# FPGA_Banks_44_45_46_DDR64.net
KiCad netlist of a schematic drawn in Altium Designer
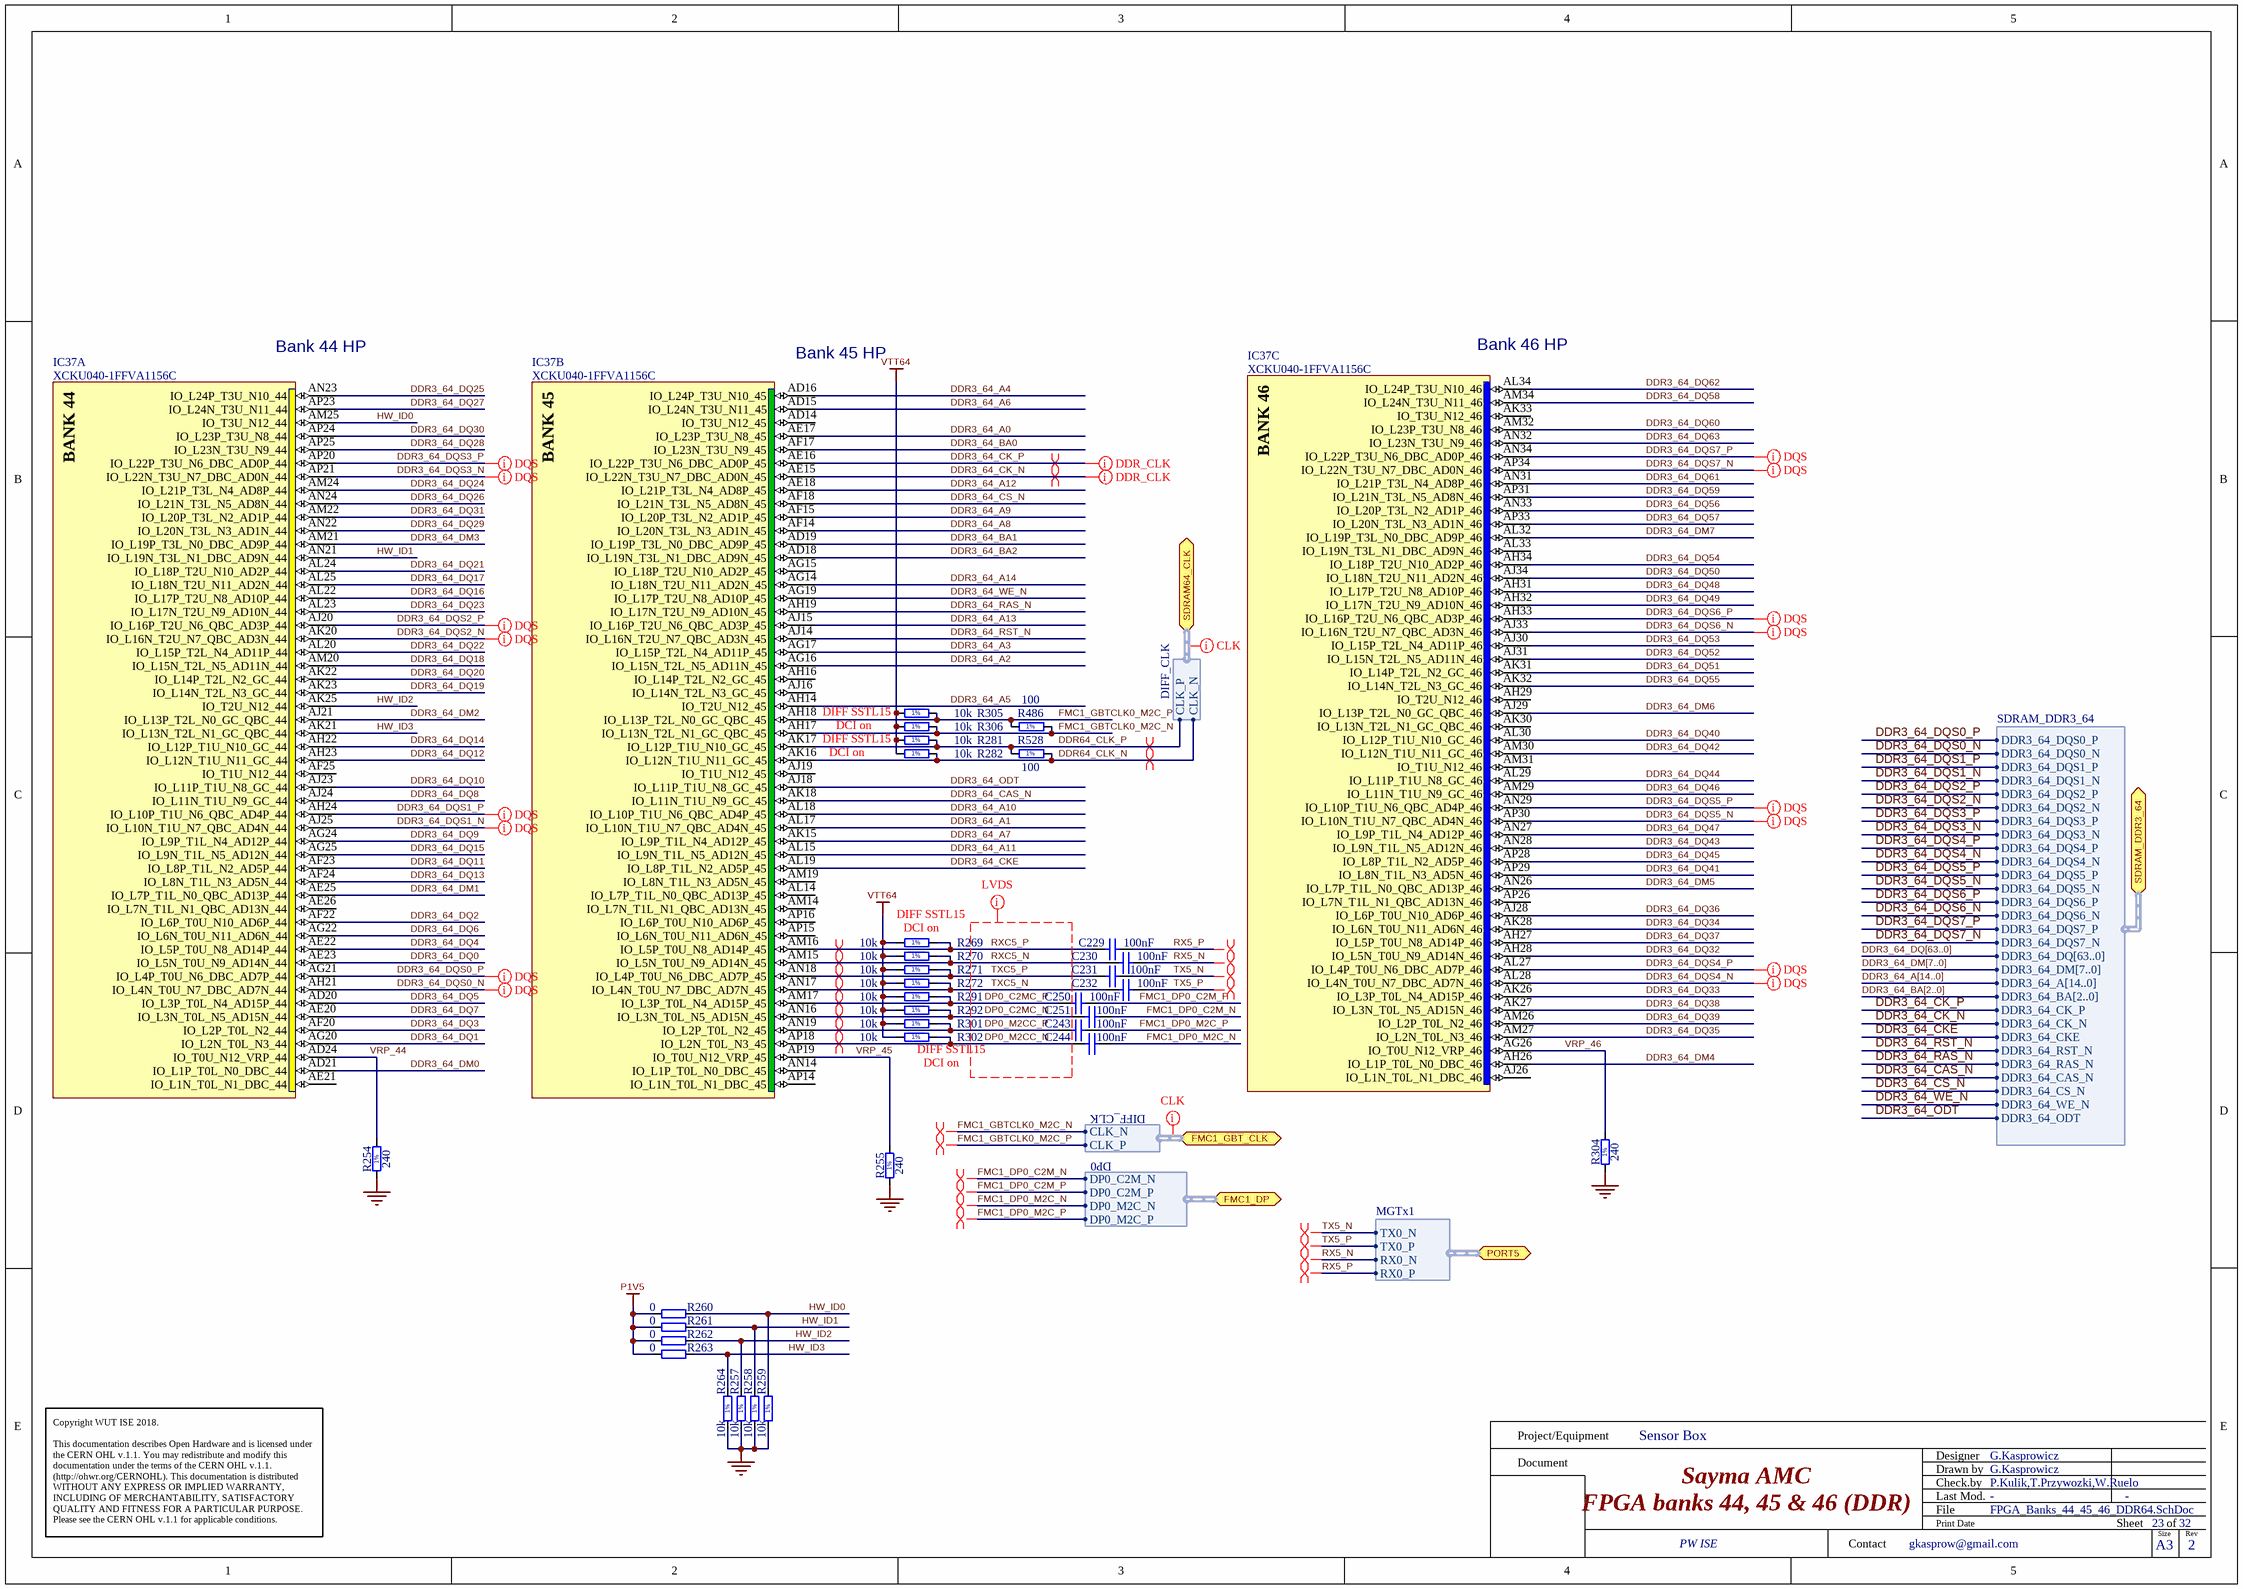
[diagram p0: FPGA_Banks_44_45_46_DDR64.SchDoc]

(export (version "E")
  (design (tool "Eeschema 10.0.6"))
  (components
    (comp (ref "C229")
      (value "100nF")
      (footprint "CAPC0603X33N")
      (description "Non-polarised capacitor")
      (fields
        (field (name "MANUFACTURER PART NUMBER") "CC0201_100NF_6.3V_10%_X5R")
        (field (name "MANUFACTURER") "GENERIC")
        (field (name "AUTHOR") "CERN DEM JLC")
      )
      (libsource (lib "Capacitors") (part "Capacitor - non polarized"))
    )
    (comp (ref "C230")
      (value "100nF")
      (footprint "CAPC0603X33N")
      (description "Non-polarised capacitor")
      (fields
        (field (name "MANUFACTURER PART NUMBER") "CC0201_100NF_6.3V_10%_X5R")
        (field (name "MANUFACTURER") "GENERIC")
        (field (name "AUTHOR") "CERN DEM JLC")
      )
      (libsource (lib "Capacitors") (part "Capacitor - non polarized"))
    )
    (comp (ref "C231")
      (value "100nF")
      (footprint "CAPC0603X33N")
      (description "Non-polarised capacitor")
      (fields
        (field (name "MANUFACTURER PART NUMBER") "CC0201_100NF_6.3V_10%_X5R")
        (field (name "MANUFACTURER") "GENERIC")
        (field (name "AUTHOR") "CERN DEM JLC")
      )
      (libsource (lib "Capacitors") (part "Capacitor - non polarized"))
    )
    (comp (ref "C232")
      (value "100nF")
      (footprint "CAPC0603X33N")
      (description "Non-polarised capacitor")
      (fields
        (field (name "MANUFACTURER PART NUMBER") "CC0201_100NF_6.3V_10%_X5R")
        (field (name "MANUFACTURER") "GENERIC")
        (field (name "AUTHOR") "CERN DEM JLC")
      )
      (libsource (lib "Capacitors") (part "Capacitor - non polarized"))
    )
    (comp (ref "C243")
      (value "100nF")
      (footprint "CAPC0603X33N")
      (description "Non-polarised capacitor")
      (fields
        (field (name "MANUFACTURER PART NUMBER") "CC0201_100NF_6.3V_10%_X5R")
        (field (name "MANUFACTURER") "GENERIC")
        (field (name "AUTHOR") "CERN DEM JLC")
      )
      (libsource (lib "Capacitors") (part "Capacitor - non polarized"))
    )
    (comp (ref "C244")
      (value "100nF")
      (footprint "CAPC0603X33N")
      (description "Non-polarised capacitor")
      (fields
        (field (name "MANUFACTURER PART NUMBER") "CC0201_100NF_6.3V_10%_X5R")
        (field (name "MANUFACTURER") "GENERIC")
        (field (name "AUTHOR") "CERN DEM JLC")
      )
      (libsource (lib "Capacitors") (part "Capacitor - non polarized"))
    )
    (comp (ref "C250")
      (value "100nF")
      (footprint "CAPC0603X33N")
      (description "Non-polarised capacitor")
      (fields
        (field (name "MANUFACTURER PART NUMBER") "CC0201_100NF_6.3V_10%_X5R")
        (field (name "MANUFACTURER") "GENERIC")
        (field (name "AUTHOR") "CERN DEM JLC")
      )
      (libsource (lib "Capacitors") (part "Capacitor - non polarized"))
    )
    (comp (ref "C251")
      (value "100nF")
      (footprint "CAPC0603X33N")
      (description "Non-polarised capacitor")
      (fields
        (field (name "MANUFACTURER PART NUMBER") "CC0201_100NF_6.3V_10%_X5R")
        (field (name "MANUFACTURER") "GENERIC")
        (field (name "AUTHOR") "CERN DEM JLC")
      )
      (libsource (lib "Capacitors") (part "Capacitor - non polarized"))
    )
    (comp (ref "IC37")
      (value "XCKU040-1FFVA1156C")
      (footprint "BGA1156C100P34X34_3500X3500X350")
      (description "Kintex UltraScale FPGA, 520 I/O, 530K Cells, 1156-Ball BGA, Speed Grade 1, Commercial Grade")
      (fields (field (name "MANUFACTURER") "XILINX") (field (name "AUTHOR") "CERN DEM CA"))
      (libsource (lib "ICs And Semiconductors") (part "XCKU040-1FFVA1156C"))
    )
    (comp (ref "R254")
      (value "240")
      (footprint "RESC1005X40N")
      (description "Resistor - 1%")
      (fields
        (field (name "MANUFACTURER PART NUMBER") "R0402_240R_1%_0.0625W_100PPM")
        (field (name "MANUFACTURER") "GENERIC")
        (field (name "AUTHOR") "CERN DEM JLC")
      )
      (libsource (lib "Resistors") (part "Resistor - 1%"))
    )
    (comp (ref "R255")
      (value "240")
      (footprint "RESC1005X40N")
      (description "Resistor - 1%")
      (fields
        (field (name "MANUFACTURER PART NUMBER") "R0402_240R_1%_0.0625W_100PPM")
        (field (name "MANUFACTURER") "GENERIC")
        (field (name "AUTHOR") "CERN DEM JLC")
      )
      (libsource (lib "Resistors") (part "Resistor - 1%"))
    )
    (comp (ref "R257")
      (value "10k")
      (footprint "RESC1005X40N")
      (description "Resistor - 1%")
      (fields
        (field (name "MANUFACTURER PART NUMBER") "R0402_10K_1%_0.0625W_100PPM")
        (field (name "MANUFACTURER") "GENERIC")
        (field (name "AUTHOR") "CERN DEM JLC")
      )
      (libsource (lib "Resistors") (part "Resistor - 1%"))
    )
    (comp (ref "R258")
      (value "10k")
      (footprint "RESC1005X40N")
      (description "Resistor - 1%")
      (fields
        (field (name "MANUFACTURER PART NUMBER") "R0402_10K_1%_0.0625W_100PPM")
        (field (name "MANUFACTURER") "GENERIC")
        (field (name "AUTHOR") "CERN DEM JLC")
      )
      (libsource (lib "Resistors") (part "Resistor - 1%"))
    )
    (comp (ref "R259")
      (value "10k")
      (footprint "RESC1005X40N")
      (description "Resistor - 1%")
      (fields
        (field (name "MANUFACTURER PART NUMBER") "R0402_10K_1%_0.0625W_100PPM")
        (field (name "MANUFACTURER") "GENERIC")
        (field (name "AUTHOR") "CERN DEM JLC")
      )
      (libsource (lib "Resistors") (part "Resistor - 1%"))
    )
    (comp (ref "R260")
      (value "0")
      (footprint "RESC1005X40N")
      (description "Resistor")
      (fields
        (field (name "MANUFACTURER PART NUMBER") "R0402_0R_JUMPER")
        (field (name "MANUFACTURER") "GENERIC")
        (field (name "AUTHOR") "CERN DEM JLC")
      )
      (libsource (lib "Resistors") (part "Resistor"))
    )
    (comp (ref "R261")
      (value "0")
      (footprint "RESC1005X40N")
      (description "Resistor")
      (fields
        (field (name "MANUFACTURER PART NUMBER") "R0402_0R_JUMPER")
        (field (name "MANUFACTURER") "GENERIC")
        (field (name "AUTHOR") "CERN DEM JLC")
      )
      (libsource (lib "Resistors") (part "Resistor"))
    )
    (comp (ref "R262")
      (value "0")
      (footprint "RESC1005X40N")
      (description "Resistor")
      (fields
        (field (name "MANUFACTURER PART NUMBER") "R0402_0R_JUMPER")
        (field (name "MANUFACTURER") "GENERIC")
        (field (name "AUTHOR") "CERN DEM JLC")
      )
      (libsource (lib "Resistors") (part "Resistor"))
    )
    (comp (ref "R263")
      (value "0")
      (footprint "RESC1005X40N")
      (description "Resistor")
      (fields
        (field (name "MANUFACTURER PART NUMBER") "R0402_0R_JUMPER")
        (field (name "MANUFACTURER") "GENERIC")
        (field (name "AUTHOR") "CERN DEM JLC")
      )
      (libsource (lib "Resistors") (part "Resistor"))
    )
    (comp (ref "R264")
      (value "10k")
      (footprint "RESC1005X40N")
      (description "Resistor - 1%")
      (fields
        (field (name "MANUFACTURER PART NUMBER") "R0402_10K_1%_0.0625W_100PPM")
        (field (name "MANUFACTURER") "GENERIC")
        (field (name "AUTHOR") "CERN DEM JLC")
      )
      (libsource (lib "Resistors") (part "Resistor - 1%"))
    )
    (comp (ref "R269")
      (value "10k")
      (footprint "RESC1005X40N")
      (description "Resistor - 1%")
      (fields
        (field (name "MANUFACTURER PART NUMBER") "R0402_10K_1%_0.0625W_100PPM")
        (field (name "MANUFACTURER") "GENERIC")
        (field (name "AUTHOR") "CERN DEM JLC")
      )
      (libsource (lib "Resistors") (part "Resistor - 1%"))
    )
    (comp (ref "R270")
      (value "10k")
      (footprint "RESC1005X40N")
      (description "Resistor - 1%")
      (fields
        (field (name "MANUFACTURER PART NUMBER") "R0402_10K_1%_0.0625W_100PPM")
        (field (name "MANUFACTURER") "GENERIC")
        (field (name "AUTHOR") "CERN DEM JLC")
      )
      (libsource (lib "Resistors") (part "Resistor - 1%"))
    )
    (comp (ref "R271")
      (value "10k")
      (footprint "RESC1005X40N")
      (description "Resistor - 1%")
      (fields
        (field (name "MANUFACTURER PART NUMBER") "R0402_10K_1%_0.0625W_100PPM")
        (field (name "MANUFACTURER") "GENERIC")
        (field (name "AUTHOR") "CERN DEM JLC")
      )
      (libsource (lib "Resistors") (part "Resistor - 1%"))
    )
    (comp (ref "R272")
      (value "10k")
      (footprint "RESC1005X40N")
      (description "Resistor - 1%")
      (fields
        (field (name "MANUFACTURER PART NUMBER") "R0402_10K_1%_0.0625W_100PPM")
        (field (name "MANUFACTURER") "GENERIC")
        (field (name "AUTHOR") "CERN DEM JLC")
      )
      (libsource (lib "Resistors") (part "Resistor - 1%"))
    )
    (comp (ref "R281")
      (value "10k")
      (footprint "RESC1005X40N")
      (description "Resistor - 1%")
      (fields
        (field (name "MANUFACTURER PART NUMBER") "R0402_10K_1%_0.0625W_100PPM")
        (field (name "MANUFACTURER") "GENERIC")
        (field (name "AUTHOR") "CERN DEM JLC")
      )
      (libsource (lib "Resistors") (part "Resistor - 1%"))
    )
    (comp (ref "R282")
      (value "10k")
      (footprint "RESC1005X40N")
      (description "Resistor - 1%")
      (fields
        (field (name "MANUFACTURER PART NUMBER") "R0402_10K_1%_0.0625W_100PPM")
        (field (name "MANUFACTURER") "GENERIC")
        (field (name "AUTHOR") "CERN DEM JLC")
      )
      (libsource (lib "Resistors") (part "Resistor - 1%"))
    )
    (comp (ref "R291")
      (value "10k")
      (footprint "RESC1005X40N")
      (description "Resistor - 1%")
      (fields
        (field (name "MANUFACTURER PART NUMBER") "R0402_10K_1%_0.0625W_100PPM")
        (field (name "MANUFACTURER") "GENERIC")
        (field (name "AUTHOR") "CERN DEM JLC")
      )
      (libsource (lib "Resistors") (part "Resistor - 1%"))
    )
    (comp (ref "R292")
      (value "10k")
      (footprint "RESC1005X40N")
      (description "Resistor - 1%")
      (fields
        (field (name "MANUFACTURER PART NUMBER") "R0402_10K_1%_0.0625W_100PPM")
        (field (name "MANUFACTURER") "GENERIC")
        (field (name "AUTHOR") "CERN DEM JLC")
      )
      (libsource (lib "Resistors") (part "Resistor - 1%"))
    )
    (comp (ref "R301")
      (value "10k")
      (footprint "RESC1005X40N")
      (description "Resistor - 1%")
      (fields
        (field (name "MANUFACTURER PART NUMBER") "R0402_10K_1%_0.0625W_100PPM")
        (field (name "MANUFACTURER") "GENERIC")
        (field (name "AUTHOR") "CERN DEM JLC")
      )
      (libsource (lib "Resistors") (part "Resistor - 1%"))
    )
    (comp (ref "R302")
      (value "10k")
      (footprint "RESC1005X40N")
      (description "Resistor - 1%")
      (fields
        (field (name "MANUFACTURER PART NUMBER") "R0402_10K_1%_0.0625W_100PPM")
        (field (name "MANUFACTURER") "GENERIC")
        (field (name "AUTHOR") "CERN DEM JLC")
      )
      (libsource (lib "Resistors") (part "Resistor - 1%"))
    )
    (comp (ref "R304")
      (value "240")
      (footprint "RESC1005X40N")
      (description "Resistor - 1%")
      (fields
        (field (name "MANUFACTURER PART NUMBER") "R0402_240R_1%_0.0625W_100PPM")
        (field (name "MANUFACTURER") "GENERIC")
        (field (name "AUTHOR") "CERN DEM JLC")
      )
      (libsource (lib "Resistors") (part "Resistor - 1%"))
    )
    (comp (ref "R305")
      (value "10k")
      (footprint "RESC1005X40N")
      (description "Resistor - 1%")
      (fields
        (field (name "MANUFACTURER PART NUMBER") "R0402_10K_1%_0.0625W_100PPM")
        (field (name "MANUFACTURER") "GENERIC")
        (field (name "AUTHOR") "CERN DEM JLC")
      )
      (libsource (lib "Resistors") (part "Resistor - 1%"))
    )
    (comp (ref "R306")
      (value "10k")
      (footprint "RESC1005X40N")
      (description "Resistor - 1%")
      (fields
        (field (name "MANUFACTURER PART NUMBER") "R0402_10K_1%_0.0625W_100PPM")
        (field (name "MANUFACTURER") "GENERIC")
        (field (name "AUTHOR") "CERN DEM JLC")
      )
      (libsource (lib "Resistors") (part "Resistor - 1%"))
    )
    (comp (ref "R486")
      (value "100")
      (footprint "RESC0603X28N")
      (description "Resistor - 1%")
      (fields
        (field (name "MANUFACTURER PART NUMBER") "R0201_100R_1%_0.05W_200PPM")
        (field (name "MANUFACTURER") "GENERIC")
        (field (name "AUTHOR") "CERN DEM JLC")
      )
      (libsource (lib "Resistors") (part "Resistor - 1%"))
    )
    (comp (ref "R528")
      (value "100")
      (footprint "RESC0603X28N")
      (description "Resistor - 1%")
      (fields
        (field (name "MANUFACTURER PART NUMBER") "R0201_100R_1%_0.05W_200PPM")
        (field (name "MANUFACTURER") "GENERIC")
        (field (name "AUTHOR") "CERN DEM JLC")
      )
      (libsource (lib "Resistors") (part "Resistor - 1%"))
    )
  )
  (nets
    (net (code "5") (name "/DDR3_64_A0") (class "Default")
      (node (ref "IC37") (pin "AE17") (pinfunction "IO_L23P_T3U_N8_45_AE17") (pintype "bidirectional"))
    )
    (net (code "6") (name "/DDR3_64_A1") (class "Default")
      (node (ref "IC37") (pin "AL17") (pinfunction "IO_L10N_T1U_N7_QBC_AD4N_45_AL17") (pintype "bidirectional"))
    )
    (net (code "7") (name "/DDR3_64_A2") (class "Default")
      (node (ref "IC37") (pin "AG16") (pinfunction "IO_L15N_T2L_N5_AD11N_45_AG16") (pintype "bidirectional"))
    )
    (net (code "8") (name "/DDR3_64_A3") (class "Default")
      (node (ref "IC37") (pin "AG17") (pinfunction "IO_L15P_T2L_N4_AD11P_45_AG17") (pintype "bidirectional"))
    )
    (net (code "9") (name "/DDR3_64_A4") (class "Default")
      (node (ref "IC37") (pin "AD16") (pinfunction "IO_L24P_T3U_N10_45_AD16") (pintype "bidirectional"))
    )
    (net (code "10") (name "/DDR3_64_A5") (class "Default")
      (node (ref "IC37") (pin "AH14") (pinfunction "IO_T2U_N12_45_AH14") (pintype "bidirectional"))
    )
    (net (code "11") (name "/DDR3_64_A6") (class "Default")
      (node (ref "IC37") (pin "AD15") (pinfunction "IO_L24N_T3U_N11_45_AD15") (pintype "bidirectional"))
    )
    (net (code "12") (name "/DDR3_64_A7") (class "Default")
      (node (ref "IC37") (pin "AK15") (pinfunction "IO_L9P_T1L_N4_AD12P_45_AK15") (pintype "bidirectional"))
    )
    (net (code "13") (name "/DDR3_64_A8") (class "Default")
      (node (ref "IC37") (pin "AF14") (pinfunction "IO_L20N_T3L_N3_AD1N_45_AF14") (pintype "bidirectional"))
    )
    (net (code "14") (name "/DDR3_64_A9") (class "Default")
      (node (ref "IC37") (pin "AF15") (pinfunction "IO_L20P_T3L_N2_AD1P_45_AF15") (pintype "bidirectional"))
    )
    (net (code "15") (name "/DDR3_64_A10") (class "Default")
      (node (ref "IC37") (pin "AL18") (pinfunction "IO_L10P_T1U_N6_QBC_AD4P_45_AL18") (pintype "bidirectional"))
    )
    (net (code "16") (name "/DDR3_64_A11") (class "Default")
      (node (ref "IC37") (pin "AL15") (pinfunction "IO_L9N_T1L_N5_AD12N_45_AL15") (pintype "bidirectional"))
    )
    (net (code "17") (name "/DDR3_64_A12") (class "Default")
      (node (ref "IC37") (pin "AE18") (pinfunction "IO_L21P_T3L_N4_AD8P_45_AE18") (pintype "bidirectional"))
    )
    (net (code "18") (name "/DDR3_64_A13") (class "Default")
      (node (ref "IC37") (pin "AJ15") (pinfunction "IO_L16P_T2U_N6_QBC_AD3P_45_AJ15") (pintype "bidirectional"))
    )
    (net (code "19") (name "/DDR3_64_A14") (class "Default")
      (node (ref "IC37") (pin "AG14") (pinfunction "IO_L18N_T2U_N11_AD2N_45_AG14") (pintype "bidirectional"))
    )
    (net (code "21") (name "/DDR3_64_BA0") (class "Default")
      (node (ref "IC37") (pin "AF17") (pinfunction "IO_L23N_T3U_N9_45_AF17") (pintype "bidirectional"))
    )
    (net (code "22") (name "/DDR3_64_BA1") (class "Default")
      (node (ref "IC37") (pin "AD19") (pinfunction "IO_L19P_T3L_N0_DBC_AD9P_45_AD19") (pintype "bidirectional"))
    )
    (net (code "23") (name "/DDR3_64_BA2") (class "Default")
      (node (ref "IC37") (pin "AD18") (pinfunction "IO_L19N_T3L_N1_DBC_AD9N_45_AD18") (pintype "bidirectional"))
    )
    (net (code "25") (name "/DDR3_64_CAS_N") (class "Default")
      (node (ref "IC37") (pin "AK18") (pinfunction "IO_L11N_T1U_N9_GC_45_AK18") (pintype "bidirectional"))
    )
    (net (code "26") (name "/DDR3_64_CKE") (class "Default")
      (node (ref "IC37") (pin "AL19") (pinfunction "IO_L8P_T1L_N2_AD5P_45_AL19") (pintype "bidirectional"))
    )
    (net (code "27") (name "/DDR3_64_CK_N") (class "Default")
      (node (ref "IC37") (pin "AE15") (pinfunction "IO_L22N_T3U_N7_DBC_AD0N_45_AE15") (pintype "bidirectional"))
    )
    (net (code "28") (name "/DDR3_64_CK_P") (class "Default")
      (node (ref "IC37") (pin "AE16") (pinfunction "IO_L22P_T3U_N6_DBC_AD0P_45_AE16") (pintype "bidirectional"))
    )
    (net (code "29") (name "/DDR3_64_CS_N") (class "Default")
      (node (ref "IC37") (pin "AF18") (pinfunction "IO_L21N_T3L_N5_AD8N_45_AF18") (pintype "bidirectional"))
    )
    (net (code "30") (name "/DDR3_64_DM0") (class "Default")
      (node (ref "IC37") (pin "AD21") (pinfunction "IO_L1P_T0L_N0_DBC_44_AD21") (pintype "bidirectional"))
    )
    (net (code "31") (name "/DDR3_64_DM1") (class "Default")
      (node (ref "IC37") (pin "AE25") (pinfunction "IO_L7P_T1L_N0_QBC_AD13P_44_AE25") (pintype "bidirectional"))
    )
    (net (code "32") (name "/DDR3_64_DM2") (class "Default")
      (node (ref "IC37") (pin "AJ21") (pinfunction "IO_L13P_T2L_N0_GC_QBC_44_AJ21") (pintype "bidirectional"))
    )
    (net (code "33") (name "/DDR3_64_DM3") (class "Default")
      (node (ref "IC37") (pin "AM21") (pinfunction "IO_L19P_T3L_N0_DBC_AD9P_44_AM21") (pintype "bidirectional"))
    )
    (net (code "34") (name "/DDR3_64_DM4") (class "Default")
      (node (ref "IC37") (pin "AH26") (pinfunction "IO_L1P_T0L_N0_DBC_46_AH26") (pintype "bidirectional"))
    )
    (net (code "35") (name "/DDR3_64_DM5") (class "Default")
      (node (ref "IC37") (pin "AN26") (pinfunction "IO_L7P_T1L_N0_QBC_AD13P_46_AN26") (pintype "bidirectional"))
    )
    (net (code "36") (name "/DDR3_64_DM6") (class "Default")
      (node (ref "IC37") (pin "AJ29") (pinfunction "IO_L13P_T2L_N0_GC_QBC_46_AJ29") (pintype "bidirectional"))
    )
    (net (code "37") (name "/DDR3_64_DM7") (class "Default")
      (node (ref "IC37") (pin "AL32") (pinfunction "IO_L19P_T3L_N0_DBC_AD9P_46_AL32") (pintype "bidirectional"))
    )
    (net (code "39") (name "/DDR3_64_DQ0") (class "Default")
      (node (ref "IC37") (pin "AE23") (pinfunction "IO_L5N_T0U_N9_AD14N_44_AE23") (pintype "bidirectional"))
    )
    (net (code "40") (name "/DDR3_64_DQ1") (class "Default")
      (node (ref "IC37") (pin "AG20") (pinfunction "IO_L2N_T0L_N3_44_AG20") (pintype "bidirectional"))
    )
    (net (code "41") (name "/DDR3_64_DQ2") (class "Default")
      (node (ref "IC37") (pin "AF22") (pinfunction "IO_L6P_T0U_N10_AD6P_44_AF22") (pintype "bidirectional"))
    )
    (net (code "42") (name "/DDR3_64_DQ3") (class "Default")
      (node (ref "IC37") (pin "AF20") (pinfunction "IO_L2P_T0L_N2_44_AF20") (pintype "bidirectional"))
    )
    (net (code "43") (name "/DDR3_64_DQ4") (class "Default")
      (node (ref "IC37") (pin "AE22") (pinfunction "IO_L5P_T0U_N8_AD14P_44_AE22") (pintype "bidirectional"))
    )
    (net (code "44") (name "/DDR3_64_DQ5") (class "Default")
      (node (ref "IC37") (pin "AD20") (pinfunction "IO_L3P_T0L_N4_AD15P_44_AD20") (pintype "bidirectional"))
    )
    (net (code "45") (name "/DDR3_64_DQ6") (class "Default")
      (node (ref "IC37") (pin "AG22") (pinfunction "IO_L6N_T0U_N11_AD6N_44_AG22") (pintype "bidirectional"))
    )
    (net (code "46") (name "/DDR3_64_DQ7") (class "Default")
      (node (ref "IC37") (pin "AE20") (pinfunction "IO_L3N_T0L_N5_AD15N_44_AE20") (pintype "bidirectional"))
    )
    (net (code "47") (name "/DDR3_64_DQ8") (class "Default")
      (node (ref "IC37") (pin "AJ24") (pinfunction "IO_L11N_T1U_N9_GC_44_AJ24") (pintype "bidirectional"))
    )
    (net (code "48") (name "/DDR3_64_DQ9") (class "Default")
      (node (ref "IC37") (pin "AG24") (pinfunction "IO_L9P_T1L_N4_AD12P_44_AG24") (pintype "bidirectional"))
    )
    (net (code "49") (name "/DDR3_64_DQ10") (class "Default")
      (node (ref "IC37") (pin "AJ23") (pinfunction "IO_L11P_T1U_N8_GC_44_AJ23") (pintype "bidirectional"))
    )
    (net (code "50") (name "/DDR3_64_DQ11") (class "Default")
      (node (ref "IC37") (pin "AF23") (pinfunction "IO_L8P_T1L_N2_AD5P_44_AF23") (pintype "bidirectional"))
    )
    (net (code "51") (name "/DDR3_64_DQ12") (class "Default")
      (node (ref "IC37") (pin "AH23") (pinfunction "IO_L12N_T1U_N11_GC_44_AH23") (pintype "bidirectional"))
    )
    (net (code "52") (name "/DDR3_64_DQ13") (class "Default")
      (node (ref "IC37") (pin "AF24") (pinfunction "IO_L8N_T1L_N3_AD5N_44_AF24") (pintype "bidirectional"))
    )
    (net (code "53") (name "/DDR3_64_DQ14") (class "Default")
      (node (ref "IC37") (pin "AH22") (pinfunction "IO_L12P_T1U_N10_GC_44_AH22") (pintype "bidirectional"))
    )
    (net (code "54") (name "/DDR3_64_DQ15") (class "Default")
      (node (ref "IC37") (pin "AG25") (pinfunction "IO_L9N_T1L_N5_AD12N_44_AG25") (pintype "bidirectional"))
    )
    (net (code "55") (name "/DDR3_64_DQ16") (class "Default")
      (node (ref "IC37") (pin "AL22") (pinfunction "IO_L17P_T2U_N8_AD10P_44_AL22") (pintype "bidirectional"))
    )
    (net (code "56") (name "/DDR3_64_DQ17") (class "Default")
      (node (ref "IC37") (pin "AL25") (pinfunction "IO_L18N_T2U_N11_AD2N_44_AL25") (pintype "bidirectional"))
    )
    (net (code "57") (name "/DDR3_64_DQ18") (class "Default")
      (node (ref "IC37") (pin "AM20") (pinfunction "IO_L15N_T2L_N5_AD11N_44_AM20") (pintype "bidirectional"))
    )
    (net (code "58") (name "/DDR3_64_DQ19") (class "Default")
      (node (ref "IC37") (pin "AK23") (pinfunction "IO_L14N_T2L_N3_GC_44_AK23") (pintype "bidirectional"))
    )
    (net (code "59") (name "/DDR3_64_DQ20") (class "Default")
      (node (ref "IC37") (pin "AK22") (pinfunction "IO_L14P_T2L_N2_GC_44_AK22") (pintype "bidirectional"))
    )
    (net (code "60") (name "/DDR3_64_DQ21") (class "Default")
      (node (ref "IC37") (pin "AL24") (pinfunction "IO_L18P_T2U_N10_AD2P_44_AL24") (pintype "bidirectional"))
    )
    (net (code "61") (name "/DDR3_64_DQ22") (class "Default")
      (node (ref "IC37") (pin "AL20") (pinfunction "IO_L15P_T2L_N4_AD11P_44_AL20") (pintype "bidirectional"))
    )
    (net (code "62") (name "/DDR3_64_DQ23") (class "Default")
      (node (ref "IC37") (pin "AL23") (pinfunction "IO_L17N_T2U_N9_AD10N_44_AL23") (pintype "bidirectional"))
    )
    (net (code "63") (name "/DDR3_64_DQ24") (class "Default")
      (node (ref "IC37") (pin "AM24") (pinfunction "IO_L21P_T3L_N4_AD8P_44_AM24") (pintype "bidirectional"))
    )
    (net (code "64") (name "/DDR3_64_DQ25") (class "Default")
      (node (ref "IC37") (pin "AN23") (pinfunction "IO_L24P_T3U_N10_44_AN23") (pintype "bidirectional"))
    )
    (net (code "65") (name "/DDR3_64_DQ26") (class "Default")
      (node (ref "IC37") (pin "AN24") (pinfunction "IO_L21N_T3L_N5_AD8N_44_AN24") (pintype "bidirectional"))
    )
    (net (code "66") (name "/DDR3_64_DQ27") (class "Default")
      (node (ref "IC37") (pin "AP23") (pinfunction "IO_L24N_T3U_N11_44_AP23") (pintype "bidirectional"))
    )
    (net (code "67") (name "/DDR3_64_DQ28") (class "Default")
      (node (ref "IC37") (pin "AP25") (pinfunction "IO_L23N_T3U_N9_44_AP25") (pintype "bidirectional"))
    )
    (net (code "68") (name "/DDR3_64_DQ29") (class "Default")
      (node (ref "IC37") (pin "AN22") (pinfunction "IO_L20N_T3L_N3_AD1N_44_AN22") (pintype "bidirectional"))
    )
    (net (code "69") (name "/DDR3_64_DQ30") (class "Default")
      (node (ref "IC37") (pin "AP24") (pinfunction "IO_L23P_T3U_N8_44_AP24") (pintype "bidirectional"))
    )
    (net (code "70") (name "/DDR3_64_DQ31") (class "Default")
      (node (ref "IC37") (pin "AM22") (pinfunction "IO_L20P_T3L_N2_AD1P_44_AM22") (pintype "bidirectional"))
    )
    (net (code "71") (name "/DDR3_64_DQ32") (class "Default")
      (node (ref "IC37") (pin "AH28") (pinfunction "IO_L5N_T0U_N9_AD14N_46_AH28") (pintype "bidirectional"))
    )
    (net (code "72") (name "/DDR3_64_DQ33") (class "Default")
      (node (ref "IC37") (pin "AK26") (pinfunction "IO_L3P_T0L_N4_AD15P_46_AK26") (pintype "bidirectional"))
    )
    (net (code "73") (name "/DDR3_64_DQ34") (class "Default")
      (node (ref "IC37") (pin "AK28") (pinfunction "IO_L6N_T0U_N11_AD6N_46_AK28") (pintype "bidirectional"))
    )
    (net (code "74") (name "/DDR3_64_DQ35") (class "Default")
      (node (ref "IC37") (pin "AM27") (pinfunction "IO_L2N_T0L_N3_46_AM27") (pintype "bidirectional"))
    )
    (net (code "75") (name "/DDR3_64_DQ36") (class "Default")
      (node (ref "IC37") (pin "AJ28") (pinfunction "IO_L6P_T0U_N10_AD6P_46_AJ28") (pintype "bidirectional"))
    )
    (net (code "76") (name "/DDR3_64_DQ37") (class "Default")
      (node (ref "IC37") (pin "AH27") (pinfunction "IO_L5P_T0U_N8_AD14P_46_AH27") (pintype "bidirectional"))
    )
    (net (code "77") (name "/DDR3_64_DQ38") (class "Default")
      (node (ref "IC37") (pin "AK27") (pinfunction "IO_L3N_T0L_N5_AD15N_46_AK27") (pintype "bidirectional"))
    )
    (net (code "78") (name "/DDR3_64_DQ39") (class "Default")
      (node (ref "IC37") (pin "AM26") (pinfunction "IO_L2P_T0L_N2_46_AM26") (pintype "bidirectional"))
    )
    (net (code "79") (name "/DDR3_64_DQ40") (class "Default")
      (node (ref "IC37") (pin "AL30") (pinfunction "IO_L12P_T1U_N10_GC_46_AL30") (pintype "bidirectional"))
    )
    (net (code "80") (name "/DDR3_64_DQ41") (class "Default")
      (node (ref "IC37") (pin "AP29") (pinfunction "IO_L8N_T1L_N3_AD5N_46_AP29") (pintype "bidirectional"))
    )
    (net (code "81") (name "/DDR3_64_DQ42") (class "Default")
      (node (ref "IC37") (pin "AM30") (pinfunction "IO_L12N_T1U_N11_GC_46_AM30") (pintype "bidirectional"))
    )
    (net (code "82") (name "/DDR3_64_DQ43") (class "Default")
      (node (ref "IC37") (pin "AN28") (pinfunction "IO_L9N_T1L_N5_AD12N_46_AN28") (pintype "bidirectional"))
    )
    (net (code "83") (name "/DDR3_64_DQ44") (class "Default")
      (node (ref "IC37") (pin "AL29") (pinfunction "IO_L11P_T1U_N8_GC_46_AL29") (pintype "bidirectional"))
    )
    (net (code "84") (name "/DDR3_64_DQ45") (class "Default")
      (node (ref "IC37") (pin "AP28") (pinfunction "IO_L8P_T1L_N2_AD5P_46_AP28") (pintype "bidirectional"))
    )
    (net (code "85") (name "/DDR3_64_DQ46") (class "Default")
      (node (ref "IC37") (pin "AM29") (pinfunction "IO_L11N_T1U_N9_GC_46_AM29") (pintype "bidirectional"))
    )
    (net (code "86") (name "/DDR3_64_DQ47") (class "Default")
      (node (ref "IC37") (pin "AN27") (pinfunction "IO_L9P_T1L_N4_AD12P_46_AN27") (pintype "bidirectional"))
    )
    (net (code "87") (name "/DDR3_64_DQ48") (class "Default")
      (node (ref "IC37") (pin "AH31") (pinfunction "IO_L17P_T2U_N8_AD10P_46_AH31") (pintype "bidirectional"))
    )
    (net (code "88") (name "/DDR3_64_DQ49") (class "Default")
      (node (ref "IC37") (pin "AH32") (pinfunction "IO_L17N_T2U_N9_AD10N_46_AH32") (pintype "bidirectional"))
    )
    (net (code "89") (name "/DDR3_64_DQ50") (class "Default")
      (node (ref "IC37") (pin "AJ34") (pinfunction "IO_L18N_T2U_N11_AD2N_46_AJ34") (pintype "bidirectional"))
    )
    (net (code "90") (name "/DDR3_64_DQ51") (class "Default")
      (node (ref "IC37") (pin "AK31") (pinfunction "IO_L14P_T2L_N2_GC_46_AK31") (pintype "bidirectional"))
    )
    (net (code "91") (name "/DDR3_64_DQ52") (class "Default")
      (node (ref "IC37") (pin "AJ31") (pinfunction "IO_L15N_T2L_N5_AD11N_46_AJ31") (pintype "bidirectional"))
    )
    (net (code "92") (name "/DDR3_64_DQ53") (class "Default")
      (node (ref "IC37") (pin "AJ30") (pinfunction "IO_L15P_T2L_N4_AD11P_46_AJ30") (pintype "bidirectional"))
    )
    (net (code "93") (name "/DDR3_64_DQ54") (class "Default")
      (node (ref "IC37") (pin "AH34") (pinfunction "IO_L18P_T2U_N10_AD2P_46_AH34") (pintype "bidirectional"))
    )
    (net (code "94") (name "/DDR3_64_DQ55") (class "Default")
      (node (ref "IC37") (pin "AK32") (pinfunction "IO_L14N_T2L_N3_GC_46_AK32") (pintype "bidirectional"))
    )
    (net (code "95") (name "/DDR3_64_DQ56") (class "Default")
      (node (ref "IC37") (pin "AN33") (pinfunction "IO_L20P_T3L_N2_AD1P_46_AN33") (pintype "bidirectional"))
    )
    (net (code "96") (name "/DDR3_64_DQ57") (class "Default")
      (node (ref "IC37") (pin "AP33") (pinfunction "IO_L20N_T3L_N3_AD1N_46_AP33") (pintype "bidirectional"))
    )
    (net (code "97") (name "/DDR3_64_DQ58") (class "Default")
      (node (ref "IC37") (pin "AM34") (pinfunction "IO_L24N_T3U_N11_46_AM34") (pintype "bidirectional"))
    )
    (net (code "98") (name "/DDR3_64_DQ59") (class "Default")
      (node (ref "IC37") (pin "AP31") (pinfunction "IO_L21N_T3L_N5_AD8N_46_AP31") (pintype "bidirectional"))
    )
    (net (code "99") (name "/DDR3_64_DQ60") (class "Default")
      (node (ref "IC37") (pin "AM32") (pinfunction "IO_L23P_T3U_N8_46_AM32") (pintype "bidirectional"))
    )
    (net (code "100") (name "/DDR3_64_DQ61") (class "Default")
      (node (ref "IC37") (pin "AN31") (pinfunction "IO_L21P_T3L_N4_AD8P_46_AN31") (pintype "bidirectional"))
    )
    (net (code "101") (name "/DDR3_64_DQ62") (class "Default")
      (node (ref "IC37") (pin "AL34") (pinfunction "IO_L24P_T3U_N10_46_AL34") (pintype "bidirectional"))
    )
    (net (code "102") (name "/DDR3_64_DQ63") (class "Default")
      (node (ref "IC37") (pin "AN32") (pinfunction "IO_L23N_T3U_N9_46_AN32") (pintype "bidirectional"))
    )
    (net (code "103") (name "/DDR3_64_DQS0_N") (class "Default")
      (node (ref "IC37") (pin "AH21") (pinfunction "IO_L4N_T0U_N7_DBC_AD7N_44_AH21") (pintype "bidirectional"))
    )
    (net (code "104") (name "/DDR3_64_DQS0_P") (class "Default")
      (node (ref "IC37") (pin "AG21") (pinfunction "IO_L4P_T0U_N6_DBC_AD7P_44_AG21") (pintype "bidirectional"))
    )
    (net (code "105") (name "/DDR3_64_DQS1_N") (class "Default")
      (node (ref "IC37") (pin "AJ25") (pinfunction "IO_L10N_T1U_N7_QBC_AD4N_44_AJ25") (pintype "bidirectional"))
    )
    (net (code "106") (name "/DDR3_64_DQS1_P") (class "Default")
      (node (ref "IC37") (pin "AH24") (pinfunction "IO_L10P_T1U_N6_QBC_AD4P_44_AH24") (pintype "bidirectional"))
    )
    (net (code "107") (name "/DDR3_64_DQS2_N") (class "Default")
      (node (ref "IC37") (pin "AK20") (pinfunction "IO_L16N_T2U_N7_QBC_AD3N_44_AK20") (pintype "bidirectional"))
    )
    (net (code "108") (name "/DDR3_64_DQS2_P") (class "Default")
      (node (ref "IC37") (pin "AJ20") (pinfunction "IO_L16P_T2U_N6_QBC_AD3P_44_AJ20") (pintype "bidirectional"))
    )
    (net (code "109") (name "/DDR3_64_DQS3_N") (class "Default")
      (node (ref "IC37") (pin "AP21") (pinfunction "IO_L22N_T3U_N7_DBC_AD0N_44_AP21") (pintype "bidirectional"))
    )
    (net (code "110") (name "/DDR3_64_DQS3_P") (class "Default")
      (node (ref "IC37") (pin "AP20") (pinfunction "IO_L22P_T3U_N6_DBC_AD0P_44_AP20") (pintype "bidirectional"))
    )
    (net (code "111") (name "/DDR3_64_DQS4_N") (class "Default")
      (node (ref "IC37") (pin "AL28") (pinfunction "IO_L4N_T0U_N7_DBC_AD7N_46_AL28") (pintype "bidirectional"))
    )
    (net (code "112") (name "/DDR3_64_DQS4_P") (class "Default")
      (node (ref "IC37") (pin "AL27") (pinfunction "IO_L4P_T0U_N6_DBC_AD7P_46_AL27") (pintype "bidirectional"))
    )
    (net (code "113") (name "/DDR3_64_DQS5_N") (class "Default")
      (node (ref "IC37") (pin "AP30") (pinfunction "IO_L10N_T1U_N7_QBC_AD4N_46_AP30") (pintype "bidirectional"))
    )
    (net (code "114") (name "/DDR3_64_DQS5_P") (class "Default")
      (node (ref "IC37") (pin "AN29") (pinfunction "IO_L10P_T1U_N6_QBC_AD4P_46_AN29") (pintype "bidirectional"))
    )
    (net (code "115") (name "/DDR3_64_DQS6_N") (class "Default")
      (node (ref "IC37") (pin "AJ33") (pinfunction "IO_L16N_T2U_N7_QBC_AD3N_46_AJ33") (pintype "bidirectional"))
    )
    (net (code "116") (name "/DDR3_64_DQS6_P") (class "Default")
      (node (ref "IC37") (pin "AH33") (pinfunction "IO_L16P_T2U_N6_QBC_AD3P_46_AH33") (pintype "bidirectional"))
    )
    (net (code "117") (name "/DDR3_64_DQS7_N") (class "Default")
      (node (ref "IC37") (pin "AP34") (pinfunction "IO_L22N_T3U_N7_DBC_AD0N_46_AP34") (pintype "bidirectional"))
    )
    (net (code "118") (name "/DDR3_64_DQS7_P") (class "Default")
      (node (ref "IC37") (pin "AN34") (pinfunction "IO_L22P_T3U_N6_DBC_AD0P_46_AN34") (pintype "bidirectional"))
    )
    (net (code "120") (name "/DDR3_64_ODT") (class "Default")
      (node (ref "IC37") (pin "AJ18") (pinfunction "IO_L11P_T1U_N8_GC_45_AJ18") (pintype "bidirectional"))
    )
    (net (code "121") (name "/DDR3_64_RAS_N") (class "Default")
      (node (ref "IC37") (pin "AH19") (pinfunction "IO_L17N_T2U_N9_AD10N_45_AH19") (pintype "bidirectional"))
    )
    (net (code "122") (name "/DDR3_64_RST_N") (class "Default")
      (node (ref "IC37") (pin "AJ14") (pinfunction "IO_L16N_T2U_N7_QBC_AD3N_45_AJ14") (pintype "bidirectional"))
    )
    (net (code "123") (name "/DDR3_64_WE_N") (class "Default")
      (node (ref "IC37") (pin "AG19") (pinfunction "IO_L17P_T2U_N8_AD10P_45_AG19") (pintype "bidirectional"))
    )
    (net (code "124") (name "/DDR64_CLK_N") (class "Default")
      (node (ref "IC37") (pin "AK16") (pinfunction "IO_L12N_T1U_N11_GC_45_AK16") (pintype "bidirectional"))
      (node (ref "R282") (pin "2") (pinfunction "2_2") (pintype "passive"))
      (node (ref "R528") (pin "2") (pinfunction "2_2") (pintype "passive"))
    )
    (net (code "125") (name "/DDR64_CLK_P") (class "Default")
      (node (ref "IC37") (pin "AK17") (pinfunction "IO_L12P_T1U_N10_GC_45_AK17") (pintype "bidirectional"))
      (node (ref "R281") (pin "2") (pinfunction "2_2") (pintype "passive"))
      (node (ref "R528") (pin "1") (pinfunction "1_1") (pintype "passive"))
    )
    (net (code "126") (name "/DP0_C2MC_N") (class "Default")
      (node (ref "C251") (pin "1") (pinfunction "1_1") (pintype "passive"))
      (node (ref "IC37") (pin "AN16") (pinfunction "IO_L3N_T0L_N5_AD15N_45_AN16") (pintype "bidirectional"))
      (node (ref "R292") (pin "2") (pinfunction "2_2") (pintype "passive"))
    )
    (net (code "127") (name "/DP0_C2MC_P") (class "Default")
      (node (ref "C250") (pin "1") (pinfunction "1_1") (pintype "passive"))
      (node (ref "IC37") (pin "AM17") (pinfunction "IO_L3P_T0L_N4_AD15P_45_AM17") (pintype "bidirectional"))
      (node (ref "R291") (pin "2") (pinfunction "2_2") (pintype "passive"))
    )
    (net (code "128") (name "/DP0_M2CC_N") (class "Default")
      (node (ref "C244") (pin "1") (pinfunction "1_1") (pintype "passive"))
      (node (ref "IC37") (pin "AP18") (pinfunction "IO_L2N_T0L_N3_45_AP18") (pintype "bidirectional"))
      (node (ref "R302") (pin "2") (pinfunction "2_2") (pintype "passive"))
    )
    (net (code "129") (name "/DP0_M2CC_P") (class "Default")
      (node (ref "C243") (pin "1") (pinfunction "1_1") (pintype "passive"))
      (node (ref "IC37") (pin "AN19") (pinfunction "IO_L2P_T0L_N2_45_AN19") (pintype "bidirectional"))
      (node (ref "R301") (pin "2") (pinfunction "2_2") (pintype "passive"))
    )
    (net (code "130") (name "/FMC1_DP0_C2M_N") (class "Default")
      (node (ref "C251") (pin "2") (pinfunction "2_2") (pintype "passive"))
    )
    (net (code "131") (name "/FMC1_DP0_C2M_P") (class "Default")
      (node (ref "C250") (pin "2") (pinfunction "2_2") (pintype "passive"))
    )
    (net (code "132") (name "/FMC1_DP0_M2C_N") (class "Default")
      (node (ref "C244") (pin "2") (pinfunction "2_2") (pintype "passive"))
    )
    (net (code "133") (name "/FMC1_DP0_M2C_P") (class "Default")
      (node (ref "C243") (pin "2") (pinfunction "2_2") (pintype "passive"))
    )
    (net (code "134") (name "/FMC1_GBTCLK0_M2C_N") (class "Default")
      (node (ref "IC37") (pin "AH17") (pinfunction "IO_L13N_T2L_N1_GC_QBC_45_AH17") (pintype "bidirectional"))
      (node (ref "R306") (pin "2") (pinfunction "2_2") (pintype "passive"))
      (node (ref "R486") (pin "2") (pinfunction "2_2") (pintype "passive"))
    )
    (net (code "135") (name "/FMC1_GBTCLK0_M2C_P") (class "Default")
      (node (ref "IC37") (pin "AH18") (pinfunction "IO_L13P_T2L_N0_GC_QBC_45_AH18") (pintype "bidirectional"))
      (node (ref "R305") (pin "2") (pinfunction "2_2") (pintype "passive"))
      (node (ref "R486") (pin "1") (pinfunction "1_1") (pintype "passive"))
    )
    (net (code "136") (name "/HW_ID0") (class "Default")
      (node (ref "IC37") (pin "AM25") (pinfunction "IO_T3U_N12_44_AM25") (pintype "bidirectional"))
      (node (ref "R259") (pin "2") (pinfunction "2_2") (pintype "passive"))
      (node (ref "R260") (pin "2") (pinfunction "2_2") (pintype "passive"))
    )
    (net (code "137") (name "/HW_ID1") (class "Default")
      (node (ref "IC37") (pin "AN21") (pinfunction "IO_L19N_T3L_N1_DBC_AD9N_44_AN21") (pintype "bidirectional"))
      (node (ref "R258") (pin "2") (pinfunction "2_2") (pintype "passive"))
      (node (ref "R261") (pin "2") (pinfunction "2_2") (pintype "passive"))
    )
    (net (code "138") (name "/HW_ID2") (class "Default")
      (node (ref "IC37") (pin "AK25") (pinfunction "IO_T2U_N12_44_AK25") (pintype "bidirectional"))
      (node (ref "R257") (pin "2") (pinfunction "2_2") (pintype "passive"))
      (node (ref "R262") (pin "2") (pinfunction "2_2") (pintype "passive"))
    )
    (net (code "139") (name "/HW_ID3") (class "Default")
      (node (ref "IC37") (pin "AK21") (pinfunction "IO_L13N_T2L_N1_GC_QBC_44_AK21") (pintype "bidirectional"))
      (node (ref "R263") (pin "2") (pinfunction "2_2") (pintype "passive"))
      (node (ref "R264") (pin "2") (pinfunction "2_2") (pintype "passive"))
    )
    (net (code "140") (name "/RX5_N") (class "Default")
      (node (ref "C230") (pin "2") (pinfunction "2_2") (pintype "passive"))
    )
    (net (code "141") (name "/RX5_P") (class "Default")
      (node (ref "C229") (pin "2") (pinfunction "2_2") (pintype "passive"))
    )
    (net (code "142") (name "/RXC5_N") (class "Default")
      (node (ref "C230") (pin "1") (pinfunction "1_1") (pintype "passive"))
      (node (ref "IC37") (pin "AM15") (pinfunction "IO_L5N_T0U_N9_AD14N_45_AM15") (pintype "bidirectional"))
      (node (ref "R270") (pin "2") (pinfunction "2_2") (pintype "passive"))
    )
    (net (code "143") (name "/RXC5_P") (class "Default")
      (node (ref "C229") (pin "1") (pinfunction "1_1") (pintype "passive"))
      (node (ref "IC37") (pin "AM16") (pinfunction "IO_L5P_T0U_N8_AD14P_45_AM16") (pintype "bidirectional"))
      (node (ref "R269") (pin "2") (pinfunction "2_2") (pintype "passive"))
    )
    (net (code "144") (name "/TX5_N") (class "Default")
      (node (ref "C231") (pin "2") (pinfunction "2_2") (pintype "passive"))
    )
    (net (code "145") (name "/TX5_P") (class "Default")
      (node (ref "C232") (pin "2") (pinfunction "2_2") (pintype "passive"))
    )
    (net (code "146") (name "/TXC5_N") (class "Default")
      (node (ref "C232") (pin "1") (pinfunction "1_1") (pintype "passive"))
      (node (ref "IC37") (pin "AN17") (pinfunction "IO_L4N_T0U_N7_DBC_AD7N_45_AN17") (pintype "bidirectional"))
      (node (ref "R272") (pin "2") (pinfunction "2_2") (pintype "passive"))
    )
    (net (code "147") (name "/TXC5_P") (class "Default")
      (node (ref "C231") (pin "1") (pinfunction "1_1") (pintype "passive"))
      (node (ref "IC37") (pin "AN18") (pinfunction "IO_L4P_T0U_N6_DBC_AD7P_45_AN18") (pintype "bidirectional"))
      (node (ref "R271") (pin "2") (pinfunction "2_2") (pintype "passive"))
    )
    (net (code "148") (name "/VRP_44") (class "Default")
      (node (ref "IC37") (pin "AD24") (pinfunction "IO_T0U_N12_VRP_44_AD24") (pintype "bidirectional"))
      (node (ref "R254") (pin "2") (pinfunction "2_2") (pintype "passive"))
    )
    (net (code "149") (name "/VRP_45") (class "Default")
      (node (ref "IC37") (pin "AP19") (pinfunction "IO_T0U_N12_VRP_45_AP19") (pintype "bidirectional"))
      (node (ref "R255") (pin "2") (pinfunction "2_2") (pintype "passive"))
    )
    (net (code "150") (name "/VRP_46") (class "Default")
      (node (ref "IC37") (pin "AG26") (pinfunction "IO_T0U_N12_VRP_46_AG26") (pintype "bidirectional"))
      (node (ref "R304") (pin "2") (pinfunction "2_2") (pintype "passive"))
    )
    (net (code "155") (name "GND") (class "Default")
      (node (ref "R254") (pin "1") (pinfunction "1_1") (pintype "passive"))
      (node (ref "R255") (pin "1") (pinfunction "1_1") (pintype "passive"))
      (node (ref "R257") (pin "1") (pinfunction "1_1") (pintype "passive"))
      (node (ref "R258") (pin "1") (pinfunction "1_1") (pintype "passive"))
      (node (ref "R259") (pin "1") (pinfunction "1_1") (pintype "passive"))
      (node (ref "R264") (pin "1") (pinfunction "1_1") (pintype "passive"))
      (node (ref "R304") (pin "1") (pinfunction "1_1") (pintype "passive"))
    )
    (net (code "156") (name "P1V5") (class "Default")
      (node (ref "R260") (pin "1") (pinfunction "1_1") (pintype "passive"))
      (node (ref "R261") (pin "1") (pinfunction "1_1") (pintype "passive"))
      (node (ref "R262") (pin "1") (pinfunction "1_1") (pintype "passive"))
      (node (ref "R263") (pin "1") (pinfunction "1_1") (pintype "passive"))
    )
    (net (code "157") (name "VTT64") (class "Default")
      (node (ref "R269") (pin "1") (pinfunction "1_1") (pintype "passive"))
      (node (ref "R270") (pin "1") (pinfunction "1_1") (pintype "passive"))
      (node (ref "R271") (pin "1") (pinfunction "1_1") (pintype "passive"))
      (node (ref "R272") (pin "1") (pinfunction "1_1") (pintype "passive"))
      (node (ref "R281") (pin "1") (pinfunction "1_1") (pintype "passive"))
      (node (ref "R282") (pin "1") (pinfunction "1_1") (pintype "passive"))
      (node (ref "R291") (pin "1") (pinfunction "1_1") (pintype "passive"))
      (node (ref "R292") (pin "1") (pinfunction "1_1") (pintype "passive"))
      (node (ref "R301") (pin "1") (pinfunction "1_1") (pintype "passive"))
      (node (ref "R302") (pin "1") (pinfunction "1_1") (pintype "passive"))
      (node (ref "R305") (pin "1") (pinfunction "1_1") (pintype "passive"))
      (node (ref "R306") (pin "1") (pinfunction "1_1") (pintype "passive"))
    )
    (net (code "158") (name "unconnected-(IC37A-IO_L1N_T0L_N1_DBC_44-PadAE21)") (class "Default")
      (node (ref "IC37") (pin "AE21") (pinfunction "IO_L1N_T0L_N1_DBC_44_AE21") (pintype "bidirectional"))
    )
    (net (code "159") (name "unconnected-(IC37A-IO_L7N_T1L_N1_QBC_AD13N_44-PadAE26)") (class "Default")
      (node (ref "IC37") (pin "AE26") (pinfunction "IO_L7N_T1L_N1_QBC_AD13N_44_AE26") (pintype "bidirectional"))
    )
    (net (code "160") (name "unconnected-(IC37A-IO_T1U_N12_44-PadAF25)") (class "Default")
      (node (ref "IC37") (pin "AF25") (pinfunction "IO_T1U_N12_44_AF25") (pintype "bidirectional"))
    )
    (net (code "161") (name "unconnected-(IC37B-IO_L1N_T0L_N1_DBC_45-PadAP14)") (class "Default")
      (node (ref "IC37") (pin "AP14") (pinfunction "IO_L1N_T0L_N1_DBC_45_AP14") (pintype "bidirectional"))
    )
    (net (code "162") (name "unconnected-(IC37B-IO_L1P_T0L_N0_DBC_45-PadAN14)") (class "Default")
      (node (ref "IC37") (pin "AN14") (pinfunction "IO_L1P_T0L_N0_DBC_45_AN14") (pintype "bidirectional"))
    )
    (net (code "163") (name "unconnected-(IC37B-IO_L6N_T0U_N11_AD6N_45-PadAP15)") (class "Default")
      (node (ref "IC37") (pin "AP15") (pinfunction "IO_L6N_T0U_N11_AD6N_45_AP15") (pintype "bidirectional"))
    )
    (net (code "164") (name "unconnected-(IC37B-IO_L6P_T0U_N10_AD6P_45-PadAP16)") (class "Default")
      (node (ref "IC37") (pin "AP16") (pinfunction "IO_L6P_T0U_N10_AD6P_45_AP16") (pintype "bidirectional"))
    )
    (net (code "165") (name "unconnected-(IC37B-IO_L7N_T1L_N1_QBC_AD13N_45-PadAM14)") (class "Default")
      (node (ref "IC37") (pin "AM14") (pinfunction "IO_L7N_T1L_N1_QBC_AD13N_45_AM14") (pintype "bidirectional"))
    )
    (net (code "166") (name "unconnected-(IC37B-IO_L7P_T1L_N0_QBC_AD13P_45-PadAL14)") (class "Default")
      (node (ref "IC37") (pin "AL14") (pinfunction "IO_L7P_T1L_N0_QBC_AD13P_45_AL14") (pintype "bidirectional"))
    )
    (net (code "167") (name "unconnected-(IC37B-IO_L8N_T1L_N3_AD5N_45-PadAM19)") (class "Default")
      (node (ref "IC37") (pin "AM19") (pinfunction "IO_L8N_T1L_N3_AD5N_45_AM19") (pintype "bidirectional"))
    )
    (net (code "168") (name "unconnected-(IC37B-IO_L14N_T2L_N3_GC_45-PadAJ16)") (class "Default")
      (node (ref "IC37") (pin "AJ16") (pinfunction "IO_L14N_T2L_N3_GC_45_AJ16") (pintype "bidirectional"))
    )
    (net (code "169") (name "unconnected-(IC37B-IO_L14P_T2L_N2_GC_45-PadAH16)") (class "Default")
      (node (ref "IC37") (pin "AH16") (pinfunction "IO_L14P_T2L_N2_GC_45_AH16") (pintype "bidirectional"))
    )
    (net (code "170") (name "unconnected-(IC37B-IO_L18P_T2U_N10_AD2P_45-PadAG15)") (class "Default")
      (node (ref "IC37") (pin "AG15") (pinfunction "IO_L18P_T2U_N10_AD2P_45_AG15") (pintype "bidirectional"))
    )
    (net (code "171") (name "unconnected-(IC37B-IO_T1U_N12_45-PadAJ19)") (class "Default")
      (node (ref "IC37") (pin "AJ19") (pinfunction "IO_T1U_N12_45_AJ19") (pintype "bidirectional"))
    )
    (net (code "172") (name "unconnected-(IC37B-IO_T3U_N12_45-PadAD14)") (class "Default")
      (node (ref "IC37") (pin "AD14") (pinfunction "IO_T3U_N12_45_AD14") (pintype "bidirectional"))
    )
    (net (code "173") (name "unconnected-(IC37C-IO_L1N_T0L_N1_DBC_46-PadAJ26)") (class "Default")
      (node (ref "IC37") (pin "AJ26") (pinfunction "IO_L1N_T0L_N1_DBC_46_AJ26") (pintype "bidirectional"))
    )
    (net (code "174") (name "unconnected-(IC37C-IO_L7N_T1L_N1_QBC_AD13N_46-PadAP26)") (class "Default")
      (node (ref "IC37") (pin "AP26") (pinfunction "IO_L7N_T1L_N1_QBC_AD13N_46_AP26") (pintype "bidirectional"))
    )
    (net (code "175") (name "unconnected-(IC37C-IO_L13N_T2L_N1_GC_QBC_46-PadAK30)") (class "Default")
      (node (ref "IC37") (pin "AK30") (pinfunction "IO_L13N_T2L_N1_GC_QBC_46_AK30") (pintype "bidirectional"))
    )
    (net (code "176") (name "unconnected-(IC37C-IO_L19N_T3L_N1_DBC_AD9N_46-PadAL33)") (class "Default")
      (node (ref "IC37") (pin "AL33") (pinfunction "IO_L19N_T3L_N1_DBC_AD9N_46_AL33") (pintype "bidirectional"))
    )
    (net (code "177") (name "unconnected-(IC37C-IO_T1U_N12_46-PadAM31)") (class "Default")
      (node (ref "IC37") (pin "AM31") (pinfunction "IO_T1U_N12_46_AM31") (pintype "bidirectional"))
    )
    (net (code "178") (name "unconnected-(IC37C-IO_T2U_N12_46-PadAH29)") (class "Default")
      (node (ref "IC37") (pin "AH29") (pinfunction "IO_T2U_N12_46_AH29") (pintype "bidirectional"))
    )
    (net (code "179") (name "unconnected-(IC37C-IO_T3U_N12_46-PadAK33)") (class "Default")
      (node (ref "IC37") (pin "AK33") (pinfunction "IO_T3U_N12_46_AK33") (pintype "bidirectional"))
    )
  )
)
